# HV-Measurement.net
KiCad netlist of a schematic drawn in Altium Designer
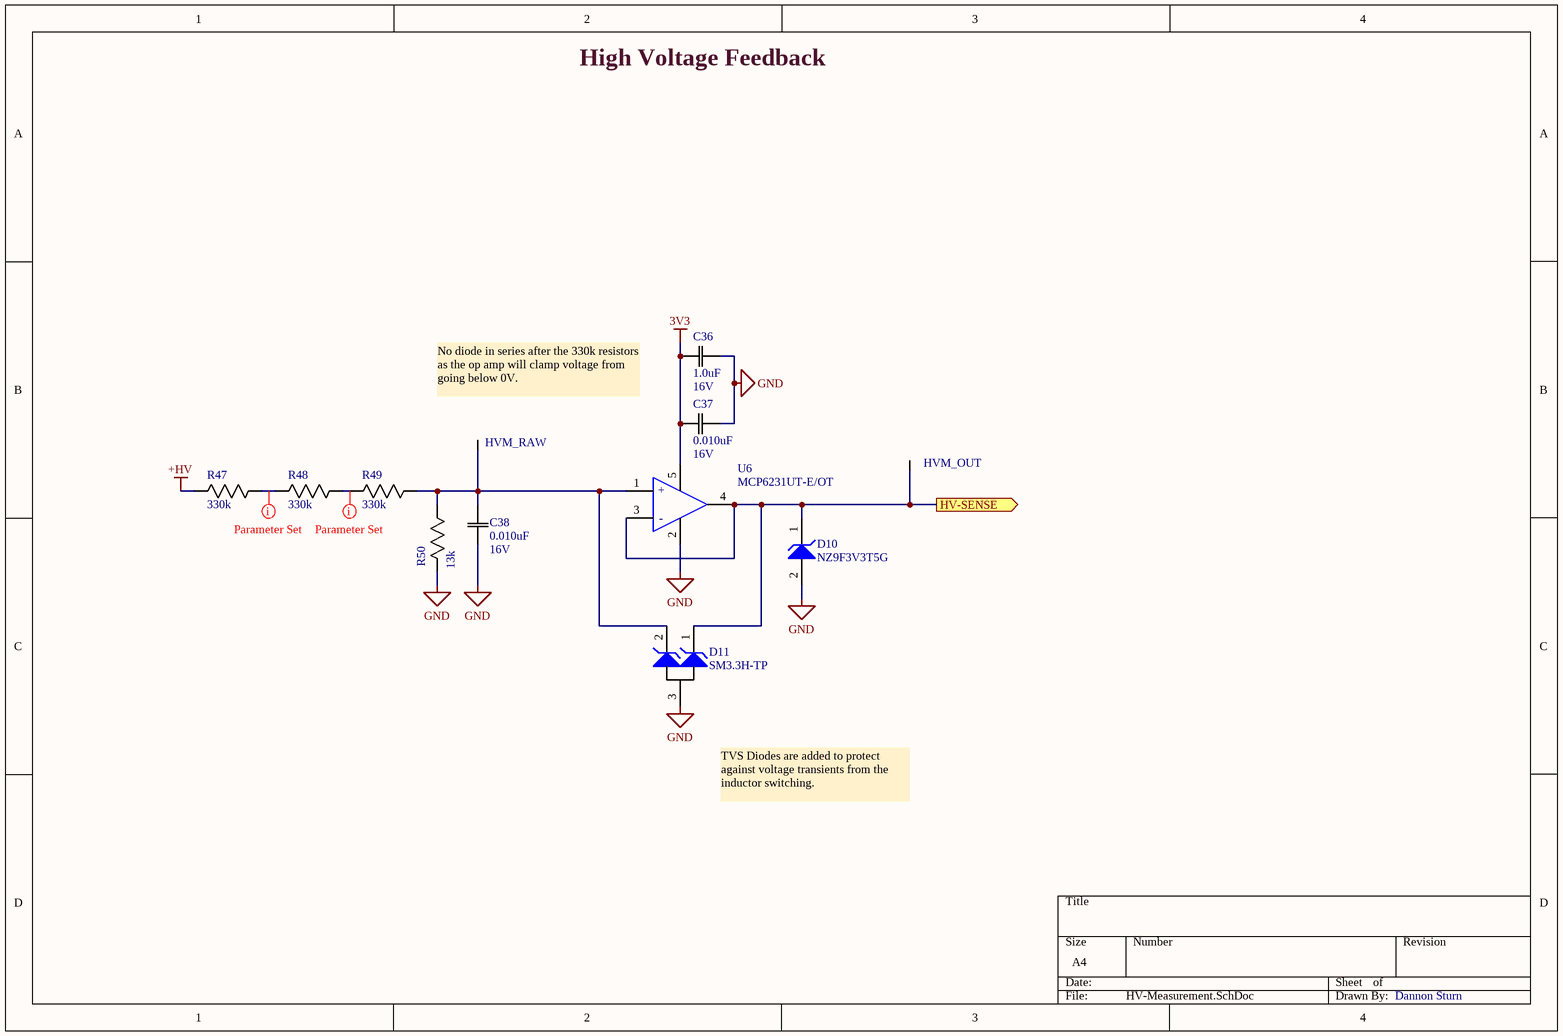
[diagram p0: HV-Measurement.SchDoc]

(export (version "E")
  (design (tool "Eeschema 10.0.6"))
  (components
    (comp (ref "C36")
      (value "1.0uF")
      (footprint "0603")
      (description "CAP CER 1.0UF 16V X5R 0603/0805")
      (fields (field (name "TOLERANCE") "10%") (field (name "RATING") "16V"))
      (libsource (lib "AltiumLibraries") (part "CAP 1.0uF 16V"))
    )
    (comp (ref "C37")
      (value "0.010uF")
      (footprint "0603")
      (description "CAP CER 0.010UF 16V X5R 0603/0805")
      (fields (field (name "TOLERANCE") "10%") (field (name "RATING") "16V"))
      (libsource (lib "AltiumLibraries") (part "CAP 0.010uF 16V"))
    )
    (comp (ref "C38")
      (value "0.010uF")
      (footprint "0603")
      (description "CAP CER 0.010UF 16V X5R 0603/0805")
      (fields (field (name "TOLERANCE") "10%") (field (name "RATING") "16V"))
      (libsource (lib "AltiumLibraries") (part "CAP 0.010uF 16V"))
    )
    (comp (ref "D10")
      (value "NZ9F3V3T5G")
      (footprint "SOD-923_0P6X0P85_ONS")
      (description "Zener Diode 3.3 V 200 mW ±5% Surface Mount SOD-923")
      (fields (field (name "COPYRIGHT") "Copyright (C) 2021 Ultra Librarian. All rights reserved."))
      (libsource (lib "AltiumLibraries") (part "DIODE ZENER 3.3 200mW"))
    )
    (comp (ref "D11")
      (value "SM3.3H-TP")
      (footprint "SOT-23A-3")
      (description "3.3V Reverese Standoff, 3.5V Breakdown, 12.5V Clamp 40A (8/20µs) Ipp Tvs Diode SMD SOT-23")
      (libsource (lib "AltiumLibraries") (part "DIODE TVS 3.3VR 3.5VBR"))
    )
    (comp (ref "HVM_OUT")
      (value "Test Point (Via)")
      (footprint "TP")
      (libsource (lib "AltiumLibraries") (part "Test Point (Via)"))
    )
    (comp (ref "HVM_RAW")
      (value "Test Point (Via)")
      (footprint "TP")
      (libsource (lib "AltiumLibraries") (part "Test Point (Via)"))
    )
    (comp (ref "R47")
      (value "330k")
      (footprint "0603")
      (description "RES SMD 330K OHM 1% 1/8W 0805/0603")
      (libsource (lib "AltiumLibraries") (part "RES 330k 1/8W - 1%"))
    )
    (comp (ref "R48")
      (value "330k")
      (footprint "0603")
      (description "RES SMD 330K OHM 1% 1/8W 0805/0603")
      (libsource (lib "AltiumLibraries") (part "RES 330k 1/8W - 1%"))
    )
    (comp (ref "R49")
      (value "330k")
      (footprint "0603")
      (description "RES SMD 330K OHM 1% 1/8W 0805/0603")
      (libsource (lib "AltiumLibraries") (part "RES 330k 1/8W - 1%"))
    )
    (comp (ref "R50")
      (value "13k")
      (footprint "0603")
      (description "RES SMD 13K OHM 5% 1/8W 0805/0603")
      (fields (field (name "TOLERANCE") "5%"))
      (libsource (lib "AltiumLibraries") (part "RES 13k 1/8W"))
    )
    (comp (ref "U6")
      (value "MCP6231UT-E/OT")
      (footprint "SOT-23-5_MC_MCH-L")
      (description "General Purpose Amplifier 1 Circuit Rail-to-Rail SOT-23-5")
      (fields (field (name "COPYRIGHT") "Copyright (C) 2021 Ultra Librarian. All rights reserved."))
      (libsource (lib "AltiumLibraries") (part "OP AMP MCP6231UT-E/OT"))
    )
  )
  (nets
    (net (code "1") (name "+HV") (class "Default")
      (node (ref "R47") (pin "2") (pinfunction "R2_2") (pintype "passive"))
    )
    (net (code "2") (name "/HV-SENSE") (class "Default")
      (node (ref "D10") (pin "1") (pinfunction "K_1") (pintype "passive"))
      (node (ref "D11") (pin "1") (pinfunction "1_1") (pintype "passive"))
      (node (ref "HVM_OUT") (pin "1") (pinfunction "1_1") (pintype "passive"))
      (node (ref "U6") (pin "3") (pinfunction "IN-_3") (pintype "tri_state"))
      (node (ref "U6") (pin "4") (pinfunction "OUT_4") (pintype "passive"))
    )
    (net (code "3") (name "3V3") (class "Default")
      (node (ref "C36") (pin "2") (pinfunction "C2_2") (pintype "passive"))
      (node (ref "C37") (pin "1") (pinfunction "C1_1") (pintype "passive"))
      (node (ref "U6") (pin "5") (pinfunction "V+_5") (pintype "power_in"))
    )
    (net (code "4") (name "GND") (class "Default")
      (node (ref "C36") (pin "1") (pinfunction "C1_1") (pintype "passive"))
      (node (ref "C37") (pin "2") (pinfunction "C2_2") (pintype "passive"))
      (node (ref "C38") (pin "1") (pinfunction "C1_1") (pintype "passive"))
      (node (ref "D10") (pin "2") (pinfunction "A_2") (pintype "passive"))
      (node (ref "D11") (pin "3") (pinfunction "3_3") (pintype "passive"))
      (node (ref "R50") (pin "2") (pinfunction "R2_2") (pintype "passive"))
      (node (ref "U6") (pin "2") (pinfunction "V-_2") (pintype "power_in"))
    )
    (net (code "5") (name "Net-(C38-C2)") (class "Default")
      (node (ref "C38") (pin "2") (pinfunction "C2_2") (pintype "passive"))
      (node (ref "D11") (pin "2") (pinfunction "2_2") (pintype "passive"))
      (node (ref "HVM_RAW") (pin "1") (pinfunction "1_1") (pintype "passive"))
      (node (ref "R49") (pin "1") (pinfunction "R1_1") (pintype "passive"))
      (node (ref "R50") (pin "1") (pinfunction "R1_1") (pintype "passive"))
      (node (ref "U6") (pin "1") (pinfunction "IN+_1") (pintype "tri_state"))
    )
    (net (code "6") (name "Net-(R47-R1)") (class "Default")
      (node (ref "R47") (pin "1") (pinfunction "R1_1") (pintype "passive"))
      (node (ref "R48") (pin "2") (pinfunction "R2_2") (pintype "passive"))
    )
    (net (code "7") (name "Net-(R48-R1)") (class "Default")
      (node (ref "R48") (pin "1") (pinfunction "R1_1") (pintype "passive"))
      (node (ref "R49") (pin "2") (pinfunction "R2_2") (pintype "passive"))
    )
  )
)
